# Sensor_Ports.net
KiCad netlist of a schematic drawn in Altium Designer
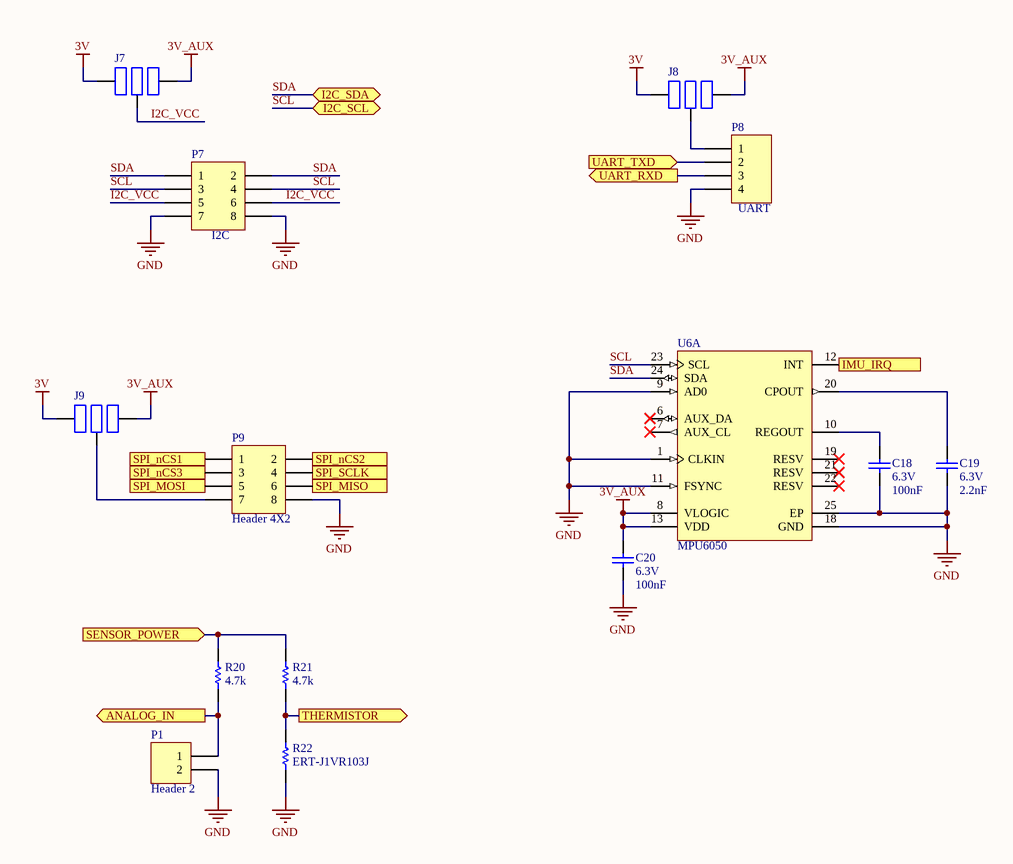
[diagram p0: Sensor Ports.SchDoc]

(export (version "E")
  (design (tool "Eeschema 10.0.6"))
  (components
    (comp (ref "C18")
      (value "100nF")
      (footprint "0603 (1608M)")
      (description "Capacitor")
      (fields (field (name "VOLTAGE") "6.3V") (field (name "Comment") "Cap"))
      (libsource (lib "components") (part "Cap"))
    )
    (comp (ref "C19")
      (value "2.2nF")
      (footprint "0603 (1608M)")
      (description "Capacitor")
      (fields (field (name "VOLTAGE") "6.3V") (field (name "Comment") "Cap"))
      (libsource (lib "components") (part "Cap"))
    )
    (comp (ref "C20")
      (value "100nF")
      (footprint "0603 (1608M)")
      (description "Capacitor")
      (fields (field (name "VOLTAGE") "6.3V") (field (name "Comment") "Cap"))
      (libsource (lib "components") (part "Cap"))
    )
    (comp (ref "J7")
      (value "3 Way Open Jumper")
      (footprint "Jumper-3 (Open)")
      (libsource (lib "components") (part "Jumper-3 (Open)"))
    )
    (comp (ref "J8")
      (value "3 Way Open Jumper")
      (footprint "Jumper-3 (Open)")
      (libsource (lib "components") (part "Jumper-3 (Open)"))
    )
    (comp (ref "J9")
      (value "3 Way Open Jumper")
      (footprint "Jumper-3 (Open)")
      (libsource (lib "components") (part "Jumper-3 (Open)"))
    )
    (comp (ref "P1")
      (value "Header 2")
      (footprint "HDR1X2")
      (description "Header, 2-Pin")
      (fields (field (name "PUBLISHER") "Altium Limited"))
      (libsource (lib "Miscellaneous Connectors") (part "Header 2"))
    )
    (comp (ref "P7")
      (value "I2C")
      (footprint "HDR2X4")
      (description "Header, 4-Pin, Dual row")
      (fields (field (name "PUBLISHER") "Altium Limited"))
      (libsource (lib "Miscellaneous Connectors") (part "Header 4X2"))
    )
    (comp (ref "P8")
      (value "UART")
      (footprint "HDR1X4")
      (description "Header, 4-Pin")
      (fields (field (name "PUBLISHER") "Altium Limited"))
      (libsource (lib "Miscellaneous Connectors") (part "Header 4"))
    )
    (comp (ref "P9")
      (value "Header 4X2")
      (footprint "HDR2X4")
      (description "Header, 4-Pin, Dual row")
      (fields (field (name "PUBLISHER") "Altium Limited"))
      (libsource (lib "Miscellaneous Connectors") (part "Header 4X2"))
    )
    (comp (ref "R20")
      (value "4.7k")
      (footprint "0603 (1608M)")
      (description "Resistor")
      (fields (field (name "TOLERANCE") "5%") (field (name "PUBLISHER") "Altium Limited"))
      (libsource (lib "components") (part "Resistor"))
    )
    (comp (ref "R21")
      (value "4.7k")
      (footprint "0603 (1608M)")
      (description "Resistor")
      (fields (field (name "TOLERANCE") "5%") (field (name "PUBLISHER") "Altium Limited"))
      (libsource (lib "components") (part "Resistor"))
    )
    (comp (ref "R22")
      (value "ERT-J1VR103J")
      (footprint "RESC1608X90X30ML15T20")
      (fields (field (name "MANUFACTURER") "Panasonic"))
      (libsource (lib "Altium Content Vault") (part "RES"))
    )
    (comp (ref "U6")
      (value "MPU6050")
      (footprint "INSE-QFN-24_V")
      (fields (field (name "TOLERANCE") "1%"))
      (libsource (lib "Altium Content Vault") (part "INSE-MPU6050-QFN-24"))
    )
  )
  (nets
    (net (code "1") (name "/ANALOG_IN") (class "Default")
      (node (ref "P1") (pin "1") (pinfunction "1_1") (pintype "passive"))
      (node (ref "R20") (pin "1") (pinfunction "1_1") (pintype "passive"))
    )
    (net (code "2") (name "/I2C_VCC") (class "Default")
      (node (ref "J7") (pin "2") (pinfunction "2_2") (pintype "passive"))
      (node (ref "P7") (pin "5") (pinfunction "5_5") (pintype "passive"))
      (node (ref "P7") (pin "6") (pinfunction "6_6") (pintype "passive"))
    )
    (net (code "3") (name "/IMU_IRQ") (class "Default")
      (node (ref "U6") (pin "12") (pinfunction "INT_12") (pintype "open_collector"))
    )
    (net (code "4") (name "/SCL") (class "Default")
      (node (ref "P7") (pin "3") (pinfunction "3_3") (pintype "passive"))
      (node (ref "P7") (pin "4") (pinfunction "4_4") (pintype "passive"))
      (node (ref "U6") (pin "23") (pinfunction "SCL_23") (pintype "input"))
    )
    (net (code "5") (name "/SDA") (class "Default")
      (node (ref "P7") (pin "1") (pinfunction "1_1") (pintype "passive"))
      (node (ref "P7") (pin "2") (pinfunction "2_2") (pintype "passive"))
      (node (ref "U6") (pin "24") (pinfunction "SDA_24") (pintype "bidirectional"))
    )
    (net (code "6") (name "/SENSOR_POWER") (class "Default")
      (node (ref "R20") (pin "2") (pinfunction "2_2") (pintype "passive"))
      (node (ref "R21") (pin "2") (pinfunction "2_2") (pintype "passive"))
    )
    (net (code "7") (name "/SPI_MISO") (class "Default")
      (node (ref "P9") (pin "6") (pinfunction "6_6") (pintype "passive"))
    )
    (net (code "8") (name "/SPI_MOSI") (class "Default")
      (node (ref "P9") (pin "5") (pinfunction "5_5") (pintype "passive"))
    )
    (net (code "9") (name "/SPI_SCLK") (class "Default")
      (node (ref "P9") (pin "4") (pinfunction "4_4") (pintype "passive"))
    )
    (net (code "10") (name "/SPI_nCS1") (class "Default")
      (node (ref "P9") (pin "1") (pinfunction "1_1") (pintype "passive"))
    )
    (net (code "11") (name "/SPI_nCS2") (class "Default")
      (node (ref "P9") (pin "2") (pinfunction "2_2") (pintype "passive"))
    )
    (net (code "12") (name "/SPI_nCS3") (class "Default")
      (node (ref "P9") (pin "3") (pinfunction "3_3") (pintype "passive"))
    )
    (net (code "13") (name "/THERMISTOR") (class "Default")
      (node (ref "R21") (pin "1") (pinfunction "1_1") (pintype "passive"))
      (node (ref "R22") (pin "2") (pinfunction "2_2") (pintype "passive"))
    )
    (net (code "14") (name "/UART_RXD") (class "Default")
      (node (ref "P8") (pin "3") (pinfunction "3_3") (pintype "passive"))
    )
    (net (code "15") (name "/UART_TXD") (class "Default")
      (node (ref "P8") (pin "2") (pinfunction "2_2") (pintype "passive"))
    )
    (net (code "16") (name "3V") (class "Default")
      (node (ref "J7") (pin "1") (pinfunction "1_1") (pintype "passive"))
      (node (ref "J8") (pin "1") (pinfunction "1_1") (pintype "passive"))
      (node (ref "J9") (pin "1") (pinfunction "1_1") (pintype "passive"))
    )
    (net (code "17") (name "3V_AUX") (class "Default")
      (node (ref "C20") (pin "2") (pinfunction "2_2") (pintype "passive"))
      (node (ref "J7") (pin "3") (pinfunction "3_3") (pintype "passive"))
      (node (ref "J8") (pin "3") (pinfunction "3_3") (pintype "passive"))
      (node (ref "J9") (pin "3") (pinfunction "3_3") (pintype "passive"))
      (node (ref "U6") (pin "13") (pinfunction "VDD_13") (pintype "power_in"))
      (node (ref "U6") (pin "8") (pinfunction "VLOGIC_8") (pintype "power_in"))
    )
    (net (code "18") (name "GND") (class "Default")
      (node (ref "C18") (pin "1") (pinfunction "1_1") (pintype "passive"))
      (node (ref "C19") (pin "1") (pinfunction "1_1") (pintype "passive"))
      (node (ref "C20") (pin "1") (pinfunction "1_1") (pintype "passive"))
      (node (ref "P1") (pin "2") (pinfunction "2_2") (pintype "passive"))
      (node (ref "P7") (pin "7") (pinfunction "7_7") (pintype "passive"))
      (node (ref "P7") (pin "8") (pinfunction "8_8") (pintype "passive"))
      (node (ref "P8") (pin "4") (pinfunction "4_4") (pintype "passive"))
      (node (ref "P9") (pin "8") (pinfunction "8_8") (pintype "passive"))
      (node (ref "R22") (pin "1") (pinfunction "1_1") (pintype "passive"))
      (node (ref "U6") (pin "1") (pinfunction "CLKIN_1") (pintype "input"))
      (node (ref "U6") (pin "11") (pinfunction "FSYNC_11") (pintype "input"))
      (node (ref "U6") (pin "18") (pinfunction "GND_18") (pintype "power_in"))
      (node (ref "U6") (pin "25") (pinfunction "EP_25") (pintype "passive"))
      (node (ref "U6") (pin "9") (pinfunction "AD0_9") (pintype "input"))
    )
    (net (code "19") (name "Net-(J8-Pad2)") (class "Default")
      (node (ref "J8") (pin "2") (pinfunction "2_2") (pintype "passive"))
      (node (ref "P8") (pin "1") (pinfunction "1_1") (pintype "passive"))
    )
    (net (code "20") (name "Net-(J9-Pad2)") (class "Default")
      (node (ref "J9") (pin "2") (pinfunction "2_2") (pintype "passive"))
      (node (ref "P9") (pin "7") (pinfunction "7_7") (pintype "passive"))
    )
    (net (code "21") (name "Net-(U6A-CPOUT)") (class "Default")
      (node (ref "C19") (pin "2") (pinfunction "2_2") (pintype "passive"))
      (node (ref "U6") (pin "20") (pinfunction "CPOUT_20") (pintype "output"))
    )
    (net (code "22") (name "Net-(U6A-REGOUT)") (class "Default")
      (node (ref "C18") (pin "2") (pinfunction "2_2") (pintype "passive"))
      (node (ref "U6") (pin "10") (pinfunction "REGOUT_10") (pintype "passive"))
    )
    (net (code "23") (name "unconnected-(U6A-AUX_CL-Pad7)") (class "Default")
      (node (ref "U6") (pin "7") (pinfunction "AUX_CL_7") (pintype "output+no_connect"))
    )
    (net (code "24") (name "unconnected-(U6A-AUX_DA-Pad6)") (class "Default")
      (node (ref "U6") (pin "6") (pinfunction "AUX_DA_6") (pintype "bidirectional+no_connect"))
    )
    (net (code "25") (name "unconnected-(U6A-RESV-Pad19)") (class "Default")
      (node (ref "U6") (pin "19") (pinfunction "RESV_19") (pintype "passive+no_connect"))
    )
    (net (code "26") (name "unconnected-(U6A-RESV-Pad21)") (class "Default")
      (node (ref "U6") (pin "21") (pinfunction "RESV_21") (pintype "passive+no_connect"))
    )
    (net (code "27") (name "unconnected-(U6A-RESV-Pad22)") (class "Default")
      (node (ref "U6") (pin "22") (pinfunction "RESV_22") (pintype "passive+no_connect"))
    )
  )
)
